# 03_USB.net
KiCad netlist of a schematic drawn in Altium Designer
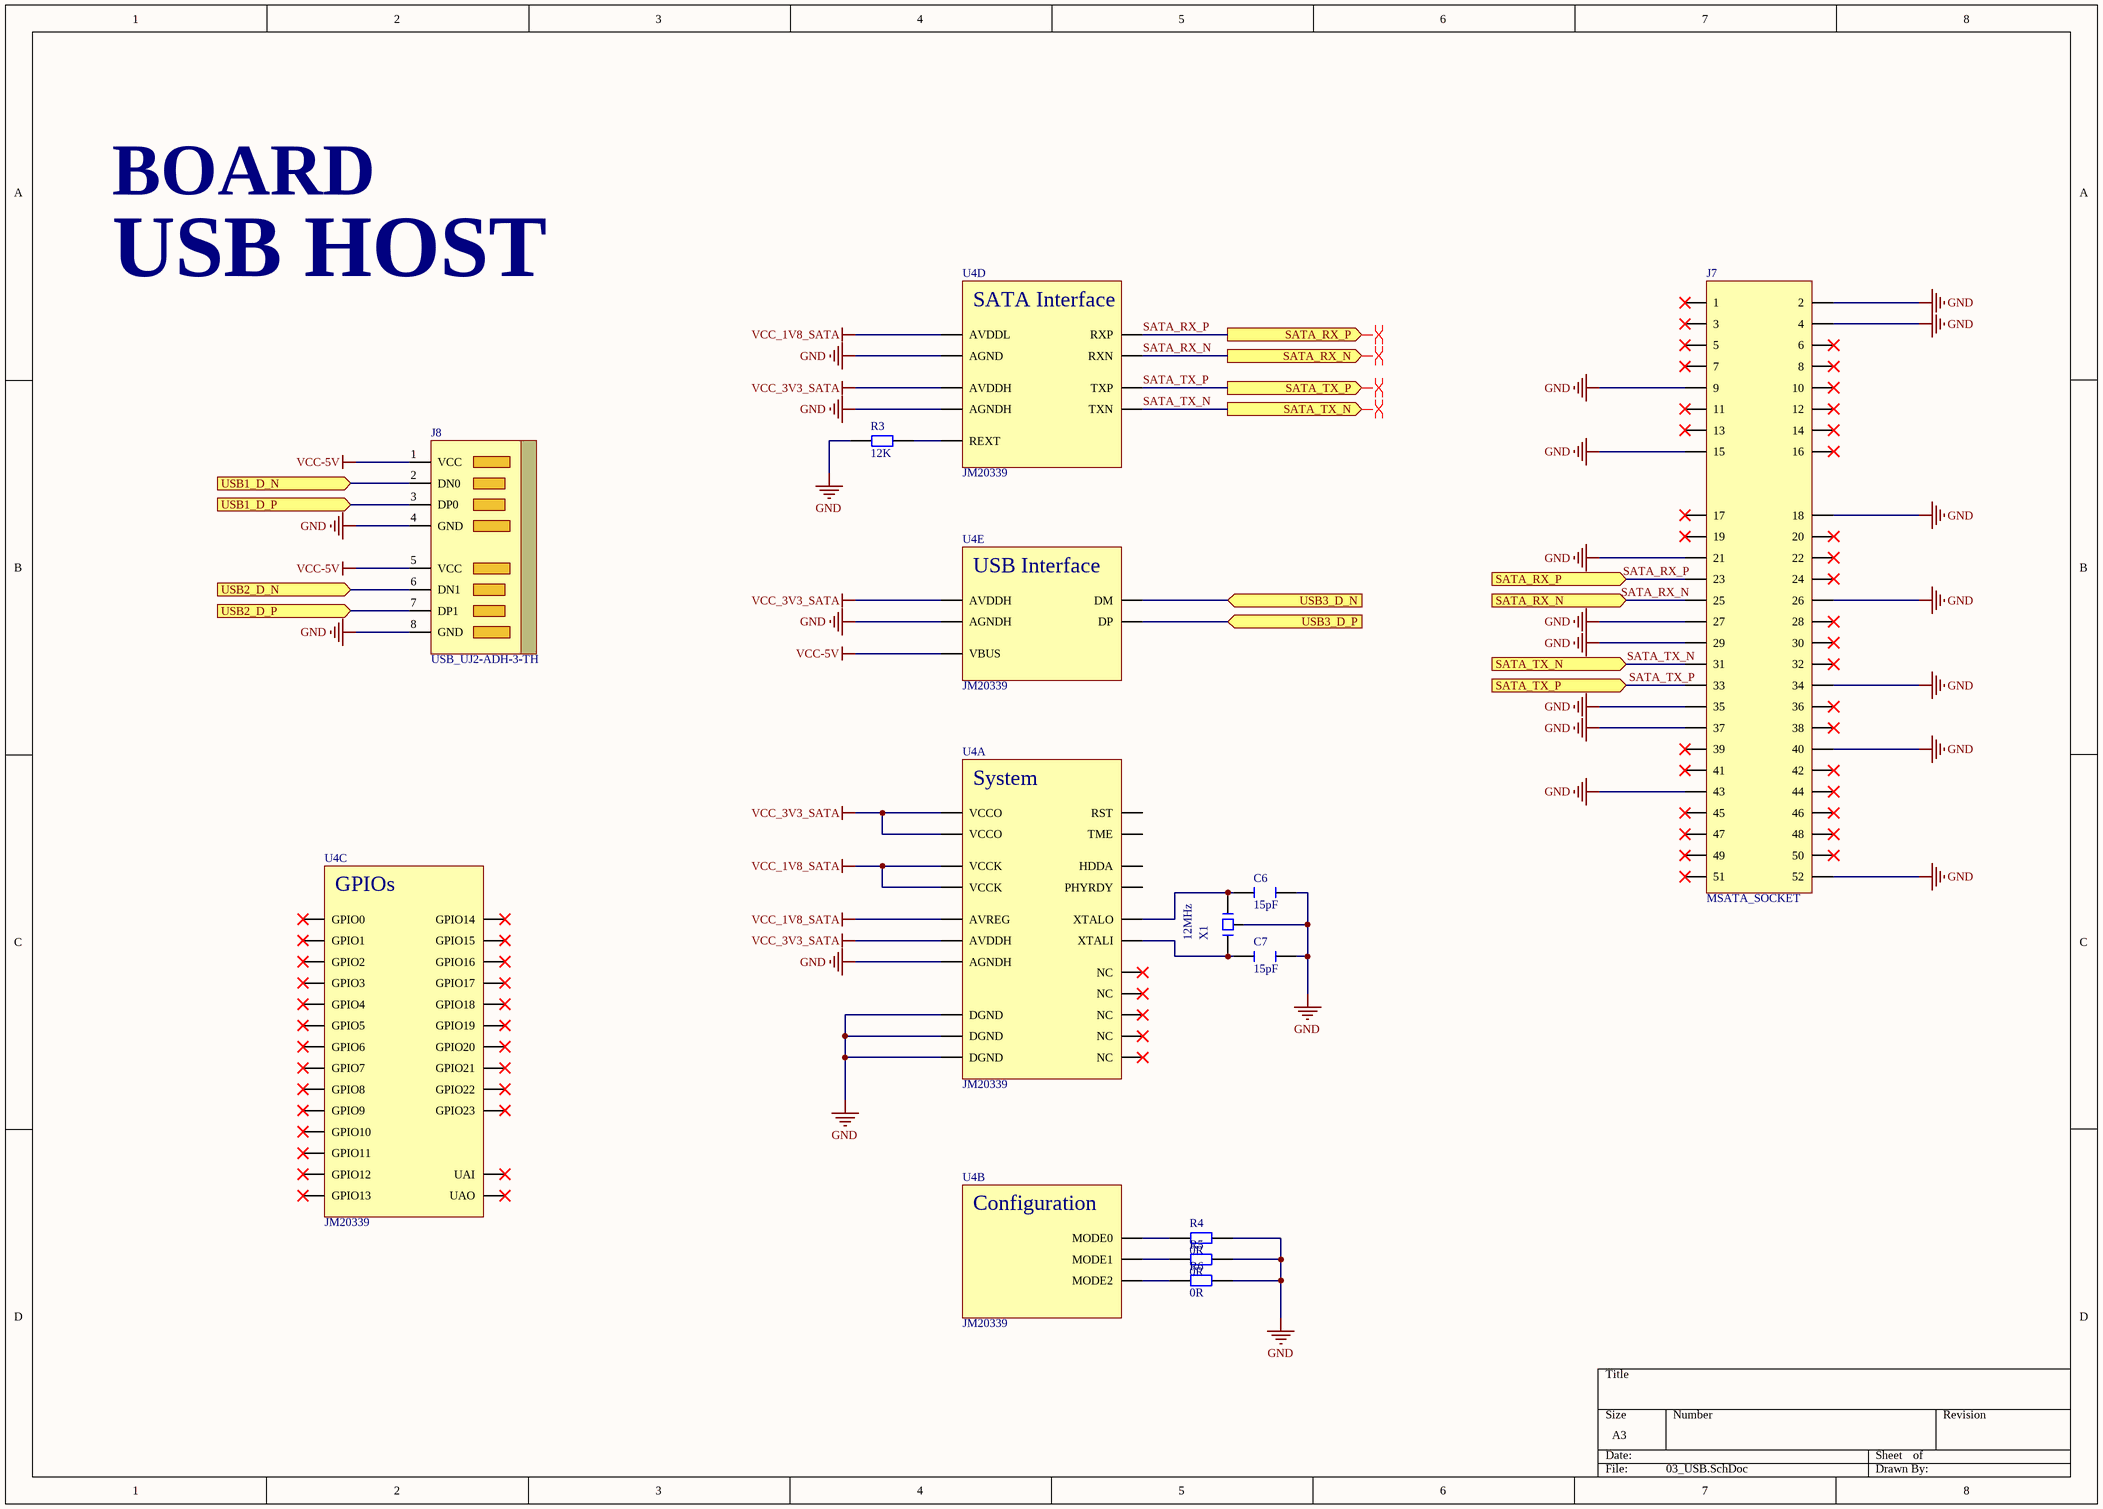
[diagram p0: 03_USB.SchDoc]

(export (version "E")
  (design (tool "Eeschema 10.0.6"))
  (components
    (comp (ref "C6") (value "15pF") (footprint "C0402") (libsource (lib "MotherBoard") (part "C_15PF")))
    (comp (ref "C7") (value "15pF") (footprint "C0402") (libsource (lib "MotherBoard") (part "C_15PF")))
    (comp (ref "J7")
      (value "MSATA_SOCKET")
      (footprint "MSATA_SOCKET")
      (libsource (lib "MotherBoard") (part "MSATA_SOCKET"))
    )
    (comp (ref "J8")
      (value "USB_UJ2-ADH-3-TH")
      (footprint "UJ2-ADH-3-TH")
      (libsource (lib "MotherBoard") (part "USB_UJ2-ADH-3-TH"))
    )
    (comp (ref "R3") (value "12K") (footprint "R0603") (libsource (lib "MotherBoard") (part "R_12K")))
    (comp (ref "R4") (value "0R") (footprint "R0603") (libsource (lib "MotherBoard") (part "R_0R")))
    (comp (ref "R5") (value "0R") (footprint "R0603") (libsource (lib "MotherBoard") (part "R_0R")))
    (comp (ref "R6") (value "0R") (footprint "R0603") (libsource (lib "MotherBoard") (part "R_0R")))
    (comp (ref "U4") (value "JM20339") (footprint "JM20339") (libsource (lib "MotherBoard") (part "JM20339")))
    (comp (ref "X1") (value "12MHz") (footprint "SMD3225") (libsource (lib "MotherBoard") (part "X_12MHZ")))
  )
  (nets
    (net (code "1") (name "/SATA_RX_N") (class "Default")
      (node (ref "J7") (pin "25") (pinfunction "25_25") (pintype "passive"))
      (node (ref "U4") (pin "28") (pinfunction "RXN_28") (pintype "passive"))
    )
    (net (code "2") (name "/SATA_RX_P") (class "Default")
      (node (ref "J7") (pin "23") (pinfunction "23_23") (pintype "passive"))
      (node (ref "U4") (pin "27") (pinfunction "RXP_27") (pintype "passive"))
    )
    (net (code "3") (name "/SATA_TX_N") (class "Default")
      (node (ref "J7") (pin "31") (pinfunction "31_31") (pintype "passive"))
      (node (ref "U4") (pin "31") (pinfunction "TXN_31") (pintype "passive"))
    )
    (net (code "4") (name "/SATA_TX_P") (class "Default")
      (node (ref "J7") (pin "33") (pinfunction "33_33") (pintype "passive"))
      (node (ref "U4") (pin "32") (pinfunction "TXP_32") (pintype "passive"))
    )
    (net (code "5") (name "/USB1_D_N") (class "Default")
      (node (ref "J8") (pin "2") (pinfunction "DN0_2") (pintype "passive"))
    )
    (net (code "6") (name "/USB1_D_P") (class "Default")
      (node (ref "J8") (pin "3") (pinfunction "DP0_3") (pintype "passive"))
    )
    (net (code "7") (name "/USB2_D_N") (class "Default")
      (node (ref "J8") (pin "6") (pinfunction "DN1_6") (pintype "passive"))
    )
    (net (code "8") (name "/USB2_D_P") (class "Default")
      (node (ref "J8") (pin "7") (pinfunction "DP1_7") (pintype "passive"))
    )
    (net (code "9") (name "/USB3_D_N") (class "Default")
      (node (ref "U4") (pin "19") (pinfunction "DM_19") (pintype "passive"))
    )
    (net (code "10") (name "/USB3_D_P") (class "Default")
      (node (ref "U4") (pin "20") (pinfunction "DP_20") (pintype "passive"))
    )
    (net (code "11") (name "GND") (class "Default")
      (node (ref "C6") (pin "2") (pinfunction "18_2") (pintype "passive"))
      (node (ref "C7") (pin "2") (pinfunction "18_2") (pintype "passive"))
      (node (ref "J7") (pin "15") (pinfunction "15_15") (pintype "passive"))
      (node (ref "J7") (pin "18") (pinfunction "18_18") (pintype "passive"))
      (node (ref "J7") (pin "2") (pinfunction "2_2") (pintype "passive"))
      (node (ref "J7") (pin "21") (pinfunction "21_21") (pintype "passive"))
      (node (ref "J7") (pin "26") (pinfunction "26_26") (pintype "passive"))
      (node (ref "J7") (pin "27") (pinfunction "27_27") (pintype "passive"))
      (node (ref "J7") (pin "29") (pinfunction "29_29") (pintype "passive"))
      (node (ref "J7") (pin "34") (pinfunction "34_34") (pintype "passive"))
      (node (ref "J7") (pin "35") (pinfunction "35_35") (pintype "passive"))
      (node (ref "J7") (pin "37") (pinfunction "37_37") (pintype "passive"))
      (node (ref "J7") (pin "4") (pinfunction "4_4") (pintype "passive"))
      (node (ref "J7") (pin "40") (pinfunction "40_40") (pintype "passive"))
      (node (ref "J7") (pin "43") (pinfunction "43_43") (pintype "passive"))
      (node (ref "J7") (pin "52") (pinfunction "52_52") (pintype "passive"))
      (node (ref "J7") (pin "9") (pinfunction "9_9") (pintype "passive"))
      (node (ref "J8") (pin "4") (pinfunction "GND_4") (pintype "passive"))
      (node (ref "J8") (pin "8") (pinfunction "GND_8") (pintype "passive"))
      (node (ref "R3") (pin "1") (pinfunction "17_1") (pintype "passive"))
      (node (ref "R4") (pin "2") (pinfunction "18_2") (pintype "passive"))
      (node (ref "R5") (pin "2") (pinfunction "18_2") (pintype "passive"))
      (node (ref "R6") (pin "2") (pinfunction "18_2") (pintype "passive"))
      (node (ref "U4") (pin "16") (pinfunction "AGNDH_16") (pintype "passive"))
      (node (ref "U4") (pin "22") (pinfunction "AGNDH_22") (pintype "passive"))
      (node (ref "U4") (pin "25") (pinfunction "AGNDH_25") (pintype "passive"))
      (node (ref "U4") (pin "30") (pinfunction "AGND_30") (pintype "passive"))
      (node (ref "U4") (pin "41") (pinfunction "DGND_41") (pintype "passive"))
      (node (ref "U4") (pin "57") (pinfunction "DGND_57") (pintype "passive"))
      (node (ref "U4") (pin "7") (pinfunction "DGND_7") (pintype "passive"))
      (node (ref "X1") (pin "3") (pinfunction "G_3") (pintype "passive"))
    )
    (net (code "12") (name "Net-(C6-17)") (class "Default")
      (node (ref "C6") (pin "1") (pinfunction "17_1") (pintype "passive"))
      (node (ref "U4") (pin "18") (pinfunction "XTALO_18") (pintype "passive"))
      (node (ref "X1") (pin "2") (pinfunction "OUT_2") (pintype "passive"))
    )
    (net (code "13") (name "Net-(C7-17)") (class "Default")
      (node (ref "C7") (pin "1") (pinfunction "17_1") (pintype "passive"))
      (node (ref "U4") (pin "17") (pinfunction "XTALI_17") (pintype "passive"))
      (node (ref "X1") (pin "1") (pinfunction "IN_1") (pintype "passive"))
    )
    (net (code "14") (name "Net-(R3-18)") (class "Default")
      (node (ref "R3") (pin "2") (pinfunction "18_2") (pintype "passive"))
      (node (ref "U4") (pin "26") (pinfunction "REXT_26") (pintype "passive"))
    )
    (net (code "15") (name "Net-(R4-17)") (class "Default")
      (node (ref "R4") (pin "1") (pinfunction "17_1") (pintype "passive"))
      (node (ref "U4") (pin "59") (pinfunction "MODE0_59") (pintype "passive"))
    )
    (net (code "16") (name "Net-(R5-17)") (class "Default")
      (node (ref "R5") (pin "1") (pinfunction "17_1") (pintype "passive"))
      (node (ref "U4") (pin "55") (pinfunction "MODE1_55") (pintype "passive"))
    )
    (net (code "17") (name "Net-(R6-17)") (class "Default")
      (node (ref "R6") (pin "1") (pinfunction "17_1") (pintype "passive"))
      (node (ref "U4") (pin "4") (pinfunction "MODE2_4") (pintype "passive"))
    )
    (net (code "18") (name "VCC-5V") (class "Default")
      (node (ref "J8") (pin "1") (pinfunction "VCC_1") (pintype "passive"))
      (node (ref "J8") (pin "5") (pinfunction "VCC_5") (pintype "passive"))
      (node (ref "U4") (pin "13") (pinfunction "VBUS_13") (pintype "passive"))
    )
    (net (code "19") (name "VCC_1V8_SATA") (class "Default")
      (node (ref "U4") (pin "14") (pinfunction "AVREG_14") (pintype "passive"))
      (node (ref "U4") (pin "29") (pinfunction "AVDDL_29") (pintype "passive"))
      (node (ref "U4") (pin "42") (pinfunction "VCCK_42") (pintype "passive"))
      (node (ref "U4") (pin "58") (pinfunction "VCCK_58") (pintype "passive"))
    )
    (net (code "20") (name "VCC_3V3_SATA") (class "Default")
      (node (ref "U4") (pin "15") (pinfunction "AVDDH_15") (pintype "passive"))
      (node (ref "U4") (pin "21") (pinfunction "AVDDH_21") (pintype "passive"))
      (node (ref "U4") (pin "24") (pinfunction "AVDDH_24") (pintype "passive"))
      (node (ref "U4") (pin "56") (pinfunction "VCCO_56") (pintype "passive"))
      (node (ref "U4") (pin "8") (pinfunction "VCCO_8") (pintype "passive"))
    )
    (net (code "21") (name "unconnected-(J7-Pad1)") (class "Default")
      (node (ref "J7") (pin "1") (pinfunction "1_1") (pintype "passive+no_connect"))
    )
    (net (code "22") (name "unconnected-(J7-Pad3)") (class "Default")
      (node (ref "J7") (pin "3") (pinfunction "3_3") (pintype "passive+no_connect"))
    )
    (net (code "23") (name "unconnected-(J7-Pad5)") (class "Default")
      (node (ref "J7") (pin "5") (pinfunction "5_5") (pintype "passive+no_connect"))
    )
    (net (code "24") (name "unconnected-(J7-Pad6)") (class "Default")
      (node (ref "J7") (pin "6") (pinfunction "6_6") (pintype "passive+no_connect"))
    )
    (net (code "25") (name "unconnected-(J7-Pad7)") (class "Default")
      (node (ref "J7") (pin "7") (pinfunction "7_7") (pintype "passive+no_connect"))
    )
    (net (code "26") (name "unconnected-(J7-Pad8)") (class "Default")
      (node (ref "J7") (pin "8") (pinfunction "8_8") (pintype "passive+no_connect"))
    )
    (net (code "27") (name "unconnected-(J7-Pad10)") (class "Default")
      (node (ref "J7") (pin "10") (pinfunction "10_10") (pintype "passive+no_connect"))
    )
    (net (code "28") (name "unconnected-(J7-Pad11)") (class "Default")
      (node (ref "J7") (pin "11") (pinfunction "11_11") (pintype "passive+no_connect"))
    )
    (net (code "29") (name "unconnected-(J7-Pad12)") (class "Default")
      (node (ref "J7") (pin "12") (pinfunction "12_12") (pintype "passive+no_connect"))
    )
    (net (code "30") (name "unconnected-(J7-Pad13)") (class "Default")
      (node (ref "J7") (pin "13") (pinfunction "13_13") (pintype "passive+no_connect"))
    )
    (net (code "31") (name "unconnected-(J7-Pad14)") (class "Default")
      (node (ref "J7") (pin "14") (pinfunction "14_14") (pintype "passive+no_connect"))
    )
    (net (code "32") (name "unconnected-(J7-Pad16)") (class "Default")
      (node (ref "J7") (pin "16") (pinfunction "16_16") (pintype "passive+no_connect"))
    )
    (net (code "33") (name "unconnected-(J7-Pad17)") (class "Default")
      (node (ref "J7") (pin "17") (pinfunction "17_17") (pintype "passive+no_connect"))
    )
    (net (code "34") (name "unconnected-(J7-Pad19)") (class "Default")
      (node (ref "J7") (pin "19") (pinfunction "19_19") (pintype "passive+no_connect"))
    )
    (net (code "35") (name "unconnected-(J7-Pad20)") (class "Default")
      (node (ref "J7") (pin "20") (pinfunction "20_20") (pintype "passive+no_connect"))
    )
    (net (code "36") (name "unconnected-(J7-Pad22)") (class "Default")
      (node (ref "J7") (pin "22") (pinfunction "22_22") (pintype "passive+no_connect"))
    )
    (net (code "37") (name "unconnected-(J7-Pad24)") (class "Default")
      (node (ref "J7") (pin "24") (pinfunction "24_24") (pintype "passive+no_connect"))
    )
    (net (code "38") (name "unconnected-(J7-Pad28)") (class "Default")
      (node (ref "J7") (pin "28") (pinfunction "28_28") (pintype "passive+no_connect"))
    )
    (net (code "39") (name "unconnected-(J7-Pad30)") (class "Default")
      (node (ref "J7") (pin "30") (pinfunction "30_30") (pintype "passive+no_connect"))
    )
    (net (code "40") (name "unconnected-(J7-Pad32)") (class "Default")
      (node (ref "J7") (pin "32") (pinfunction "32_32") (pintype "passive+no_connect"))
    )
    (net (code "41") (name "unconnected-(J7-Pad36)") (class "Default")
      (node (ref "J7") (pin "36") (pinfunction "36_36") (pintype "passive+no_connect"))
    )
    (net (code "42") (name "unconnected-(J7-Pad38)") (class "Default")
      (node (ref "J7") (pin "38") (pinfunction "38_38") (pintype "passive+no_connect"))
    )
    (net (code "43") (name "unconnected-(J7-Pad39)") (class "Default")
      (node (ref "J7") (pin "39") (pinfunction "39_39") (pintype "passive+no_connect"))
    )
    (net (code "44") (name "unconnected-(J7-Pad41)") (class "Default")
      (node (ref "J7") (pin "41") (pinfunction "41_41") (pintype "passive+no_connect"))
    )
    (net (code "45") (name "unconnected-(J7-Pad42)") (class "Default")
      (node (ref "J7") (pin "42") (pinfunction "42_42") (pintype "passive+no_connect"))
    )
    (net (code "46") (name "unconnected-(J7-Pad44)") (class "Default")
      (node (ref "J7") (pin "44") (pinfunction "44_44") (pintype "passive+no_connect"))
    )
    (net (code "47") (name "unconnected-(J7-Pad45)") (class "Default")
      (node (ref "J7") (pin "45") (pinfunction "45_45") (pintype "passive+no_connect"))
    )
    (net (code "48") (name "unconnected-(J7-Pad46)") (class "Default")
      (node (ref "J7") (pin "46") (pinfunction "46_46") (pintype "passive+no_connect"))
    )
    (net (code "49") (name "unconnected-(J7-Pad47)") (class "Default")
      (node (ref "J7") (pin "47") (pinfunction "47_47") (pintype "passive+no_connect"))
    )
    (net (code "50") (name "unconnected-(J7-Pad48)") (class "Default")
      (node (ref "J7") (pin "48") (pinfunction "48_48") (pintype "passive+no_connect"))
    )
    (net (code "51") (name "unconnected-(J7-Pad49)") (class "Default")
      (node (ref "J7") (pin "49") (pinfunction "49_49") (pintype "passive+no_connect"))
    )
    (net (code "52") (name "unconnected-(J7-Pad50)") (class "Default")
      (node (ref "J7") (pin "50") (pinfunction "50_50") (pintype "passive+no_connect"))
    )
    (net (code "53") (name "unconnected-(J7-Pad51)") (class "Default")
      (node (ref "J7") (pin "51") (pinfunction "51_51") (pintype "passive+no_connect"))
    )
    (net (code "54") (name "unconnected-(U4A-HDDA-Pad39)") (class "Default")
      (node (ref "U4") (pin "39") (pinfunction "HDDA_39") (pintype "passive"))
    )
    (net (code "55") (name "unconnected-(U4A-NC-Pad5)") (class "Default")
      (node (ref "U4") (pin "5") (pinfunction "NC_5") (pintype "passive+no_connect"))
    )
    (net (code "56") (name "unconnected-(U4A-NC-Pad6)") (class "Default")
      (node (ref "U4") (pin "6") (pinfunction "NC_6") (pintype "passive+no_connect"))
    )
    (net (code "57") (name "unconnected-(U4A-NC-Pad9)") (class "Default")
      (node (ref "U4") (pin "9") (pinfunction "NC_9") (pintype "passive+no_connect"))
    )
    (net (code "58") (name "unconnected-(U4A-NC-Pad10)") (class "Default")
      (node (ref "U4") (pin "10") (pinfunction "NC_10") (pintype "passive+no_connect"))
    )
    (net (code "59") (name "unconnected-(U4A-NC-Pad23)") (class "Default")
      (node (ref "U4") (pin "23") (pinfunction "NC_23") (pintype "passive+no_connect"))
    )
    (net (code "60") (name "unconnected-(U4A-PHYRDY-Pad38)") (class "Default")
      (node (ref "U4") (pin "38") (pinfunction "PHYRDY_38") (pintype "passive"))
    )
    (net (code "61") (name "unconnected-(U4A-RST-Pad12)") (class "Default")
      (node (ref "U4") (pin "12") (pinfunction "RST_12") (pintype "passive"))
    )
    (net (code "62") (name "unconnected-(U4A-TME-Pad37)") (class "Default")
      (node (ref "U4") (pin "37") (pinfunction "TME_37") (pintype "passive"))
    )
    (net (code "63") (name "unconnected-(U4C-GPIO0-Pad36)") (class "Default")
      (node (ref "U4") (pin "36") (pinfunction "GPIO0_36") (pintype "passive+no_connect"))
    )
    (net (code "64") (name "unconnected-(U4C-GPIO1-Pad35)") (class "Default")
      (node (ref "U4") (pin "35") (pinfunction "GPIO1_35") (pintype "passive+no_connect"))
    )
    (net (code "65") (name "unconnected-(U4C-GPIO2-Pad34)") (class "Default")
      (node (ref "U4") (pin "34") (pinfunction "GPIO2_34") (pintype "passive+no_connect"))
    )
    (net (code "66") (name "unconnected-(U4C-GPIO3-Pad33)") (class "Default")
      (node (ref "U4") (pin "33") (pinfunction "GPIO3_33") (pintype "passive+no_connect"))
    )
    (net (code "67") (name "unconnected-(U4C-GPIO4-Pad40)") (class "Default")
      (node (ref "U4") (pin "40") (pinfunction "GPIO4_40") (pintype "passive+no_connect"))
    )
    (net (code "68") (name "unconnected-(U4C-GPIO5-Pad43)") (class "Default")
      (node (ref "U4") (pin "43") (pinfunction "GPIO5_43") (pintype "passive+no_connect"))
    )
    (net (code "69") (name "unconnected-(U4C-GPIO6-Pad44)") (class "Default")
      (node (ref "U4") (pin "44") (pinfunction "GPIO6_44") (pintype "passive+no_connect"))
    )
    (net (code "70") (name "unconnected-(U4C-GPIO7-Pad11)") (class "Default")
      (node (ref "U4") (pin "11") (pinfunction "GPIO7_11") (pintype "passive+no_connect"))
    )
    (net (code "71") (name "unconnected-(U4C-GPIO8-Pad52)") (class "Default")
      (node (ref "U4") (pin "52") (pinfunction "GPIO8_52") (pintype "passive+no_connect"))
    )
    (net (code "72") (name "unconnected-(U4C-GPIO9-Pad45)") (class "Default")
      (node (ref "U4") (pin "45") (pinfunction "GPIO9_45") (pintype "passive+no_connect"))
    )
    (net (code "73") (name "unconnected-(U4C-GPIO10-Pad46)") (class "Default")
      (node (ref "U4") (pin "46") (pinfunction "GPIO10_46") (pintype "passive+no_connect"))
    )
    (net (code "74") (name "unconnected-(U4C-GPIO11-Pad47)") (class "Default")
      (node (ref "U4") (pin "47") (pinfunction "GPIO11_47") (pintype "passive+no_connect"))
    )
    (net (code "75") (name "unconnected-(U4C-GPIO12-Pad48)") (class "Default")
      (node (ref "U4") (pin "48") (pinfunction "GPIO12_48") (pintype "passive+no_connect"))
    )
    (net (code "76") (name "unconnected-(U4C-GPIO13-Pad49)") (class "Default")
      (node (ref "U4") (pin "49") (pinfunction "GPIO13_49") (pintype "passive+no_connect"))
    )
    (net (code "77") (name "unconnected-(U4C-GPIO14-Pad50)") (class "Default")
      (node (ref "U4") (pin "50") (pinfunction "GPIO14_50") (pintype "passive+no_connect"))
    )
    (net (code "78") (name "unconnected-(U4C-GPIO15-Pad51)") (class "Default")
      (node (ref "U4") (pin "51") (pinfunction "GPIO15_51") (pintype "passive+no_connect"))
    )
    (net (code "79") (name "unconnected-(U4C-GPIO16-Pad60)") (class "Default")
      (node (ref "U4") (pin "60") (pinfunction "GPIO16_60") (pintype "passive+no_connect"))
    )
    (net (code "80") (name "unconnected-(U4C-GPIO17-Pad61)") (class "Default")
      (node (ref "U4") (pin "61") (pinfunction "GPIO17_61") (pintype "passive+no_connect"))
    )
    (net (code "81") (name "unconnected-(U4C-GPIO18-Pad62)") (class "Default")
      (node (ref "U4") (pin "62") (pinfunction "GPIO18_62") (pintype "passive+no_connect"))
    )
    (net (code "82") (name "unconnected-(U4C-GPIO19-Pad63)") (class "Default")
      (node (ref "U4") (pin "63") (pinfunction "GPIO19_63") (pintype "passive+no_connect"))
    )
    (net (code "83") (name "unconnected-(U4C-GPIO20-Pad64)") (class "Default")
      (node (ref "U4") (pin "64") (pinfunction "GPIO20_64") (pintype "passive+no_connect"))
    )
    (net (code "84") (name "unconnected-(U4C-GPIO21-Pad1)") (class "Default")
      (node (ref "U4") (pin "1") (pinfunction "GPIO21_1") (pintype "passive+no_connect"))
    )
    (net (code "85") (name "unconnected-(U4C-GPIO22-Pad2)") (class "Default")
      (node (ref "U4") (pin "2") (pinfunction "GPIO22_2") (pintype "passive+no_connect"))
    )
    (net (code "86") (name "unconnected-(U4C-GPIO23-Pad3)") (class "Default")
      (node (ref "U4") (pin "3") (pinfunction "GPIO23_3") (pintype "passive+no_connect"))
    )
    (net (code "87") (name "unconnected-(U4C-UAI-Pad53)") (class "Default")
      (node (ref "U4") (pin "53") (pinfunction "UAI_53") (pintype "passive+no_connect"))
    )
    (net (code "88") (name "unconnected-(U4C-UAO-Pad54)") (class "Default")
      (node (ref "U4") (pin "54") (pinfunction "UAO_54") (pintype "passive+no_connect"))
    )
  )
)
